# Fan_Power_Out.net
KiCad netlist of a schematic drawn in Altium Designer
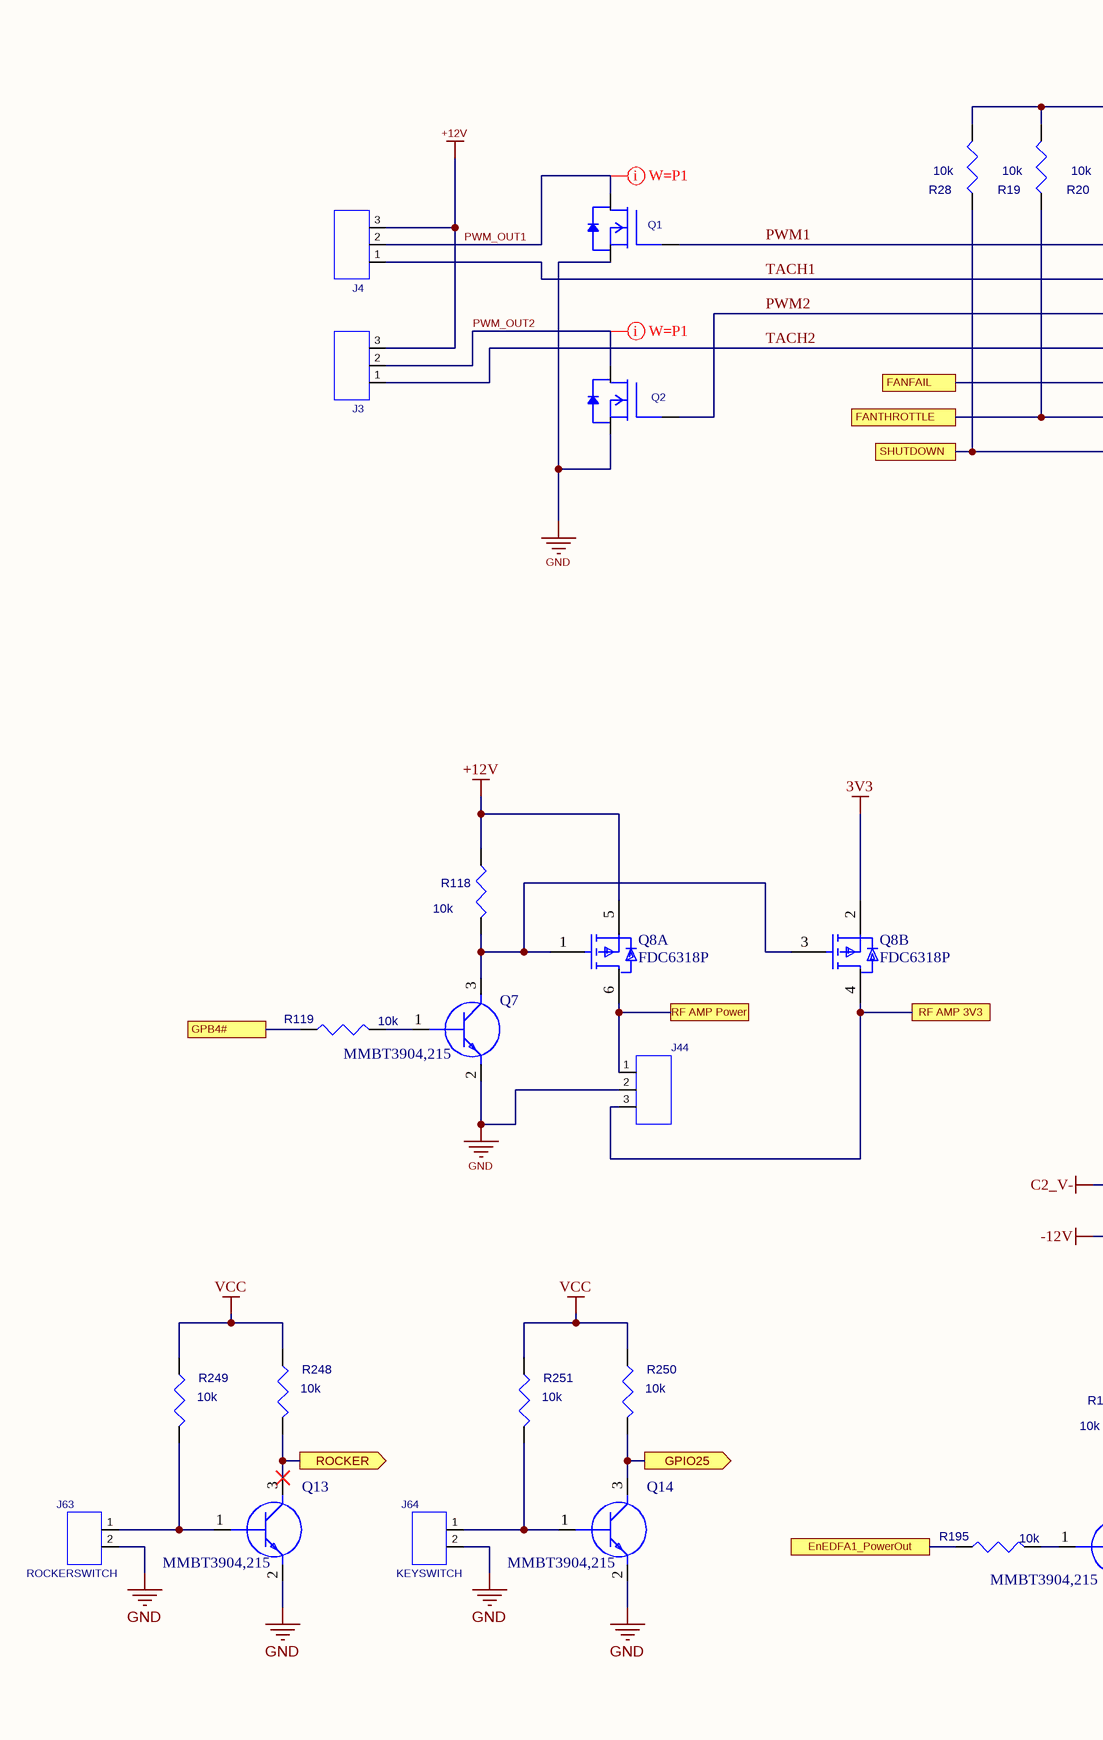
[diagram p0: Fan & Power Out.SchDoc, left]
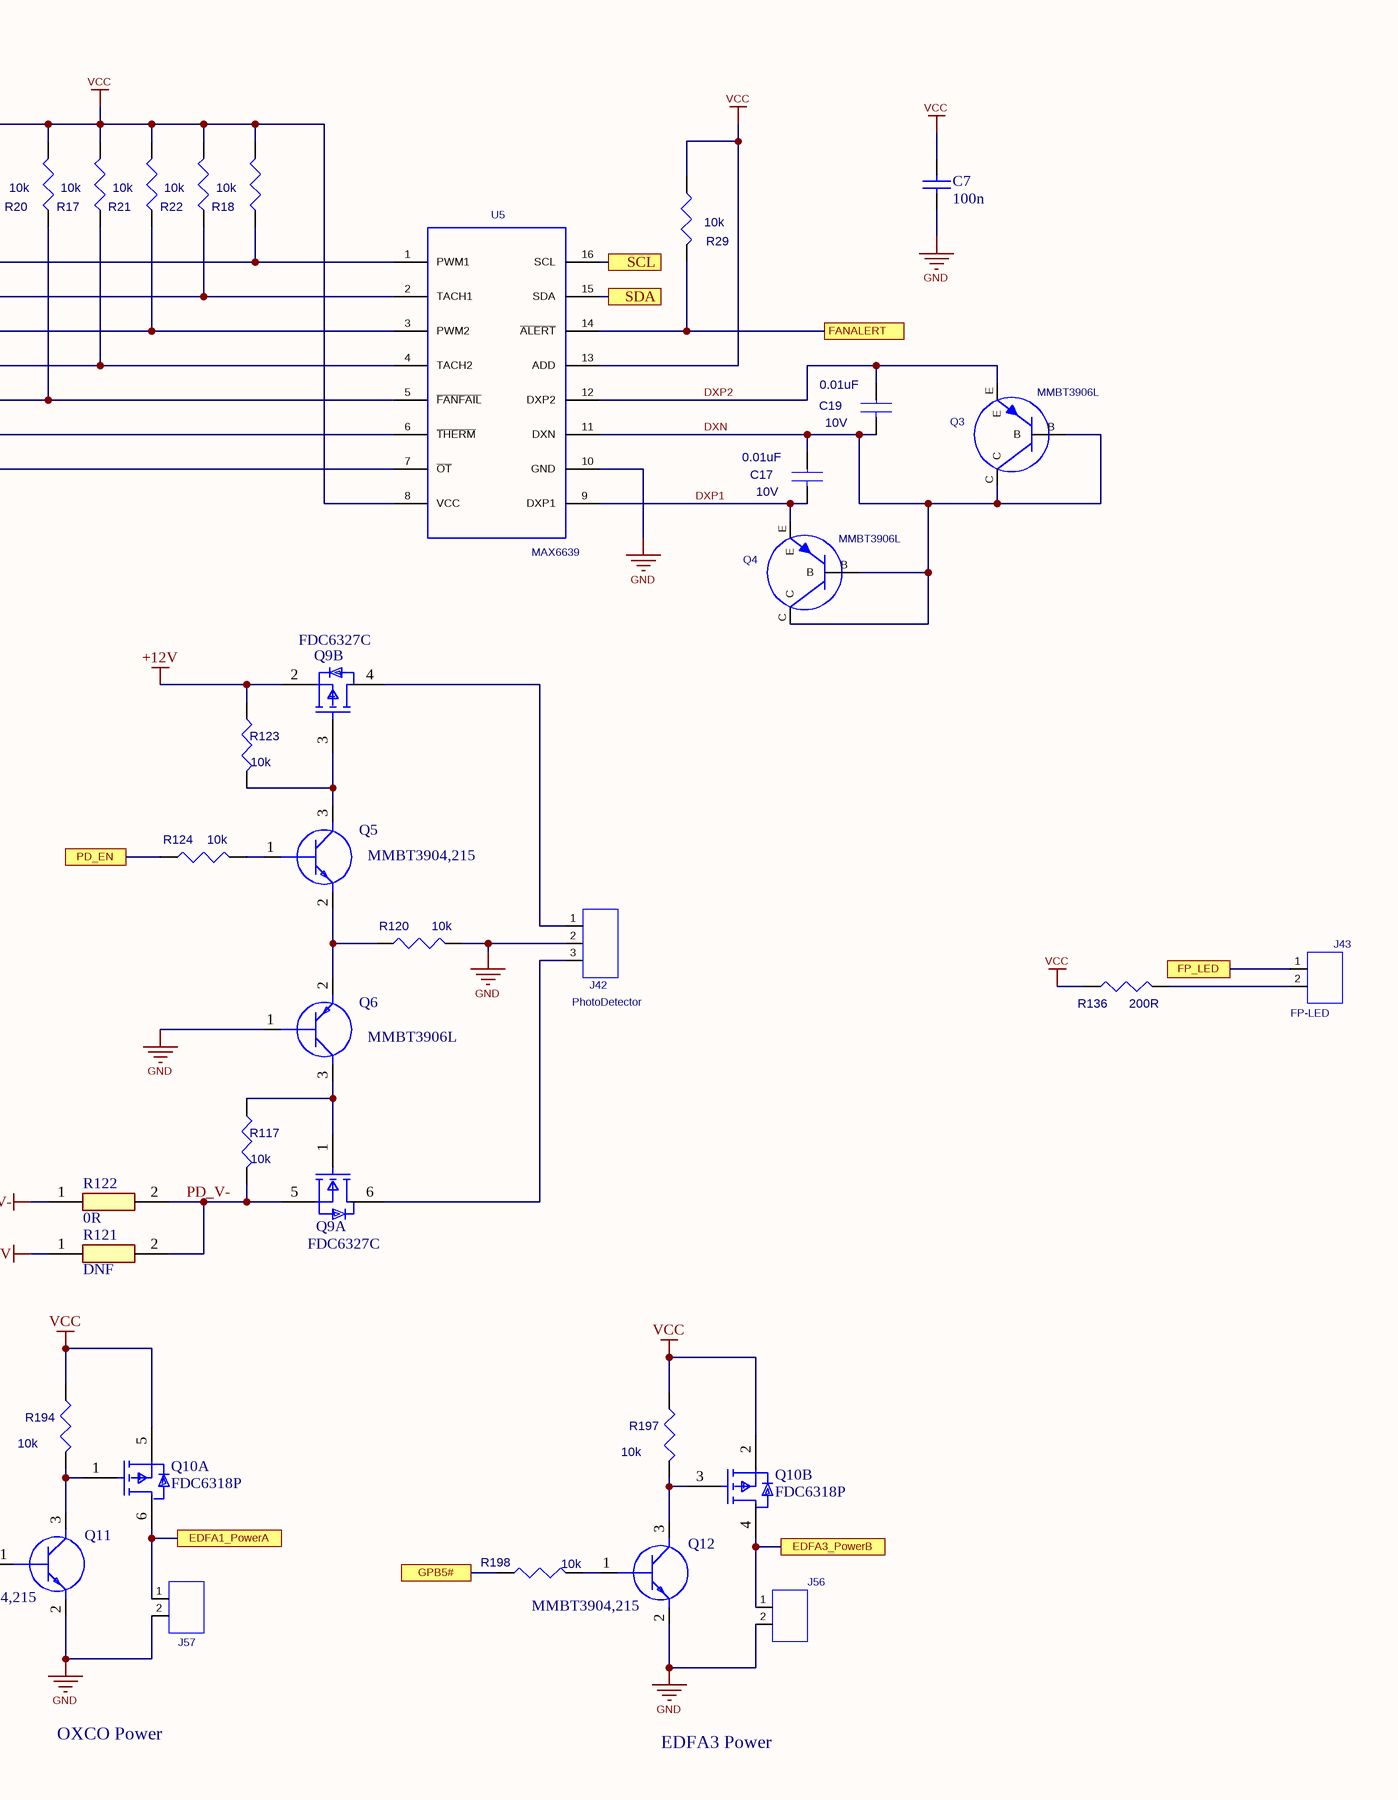
[diagram p1: Fan & Power Out.SchDoc, right]

(export (version "E")
  (design (tool "Eeschema 10.0.6"))
  (components
    (comp (ref "C7")
      (value "100n")
      (footprint "CAPC1608X90X35LL15T15")
      (description "Chip Capacitor, 100 nF, +/- 10%, 50 V, -55 to 125 degC, 0603 (1608 Metric), RoHS, Tape and Reel")
      (fields (field (name "TOLERANCE") "10%") (field (name "MANUFACTURER") "KEMET"))
      (libsource (lib "xDAC_Carrier") (part "CMP-1035-02592-3"))
    )
    (comp (ref "C17")
      (value "0.01uF")
      (footprint "CC0603N")
      (description "CAP.,0.01uF,X5R,10V,10%,0603")
      (fields
        (field (name "TOLERANCE") "10%")
        (field (name "RATED_VOLTAGE") "10V")
        (field (name "MANUFACTURER") "AVX")
      )
      (libsource (lib "xDAC_Carrier") (part "CAP"))
    )
    (comp (ref "C19")
      (value "0.01uF")
      (footprint "CC0603N")
      (description "CAP.,0.01uF,X5R,10V,10%,0603")
      (fields
        (field (name "TOLERANCE") "10%")
        (field (name "RATED_VOLTAGE") "10V")
        (field (name "MANUFACTURER") "AVX")
      )
      (libsource (lib "xDAC_Carrier") (part "CAP"))
    )
    (comp (ref "J3")
      (value "CON03")
      (footprint "AE-6410-3W-VERTICAL")
      (description "3 pin Connector")
      (fields (field (name "MANUFACTURER") "Molex") (field (name "PART NO") "22-29-2031"))
      (libsource (lib "xDAC_Carrier") (part "CON03"))
    )
    (comp (ref "J4")
      (value "CON03")
      (footprint "AE-6410-3W-VERTICAL")
      (description "3 pin Connector")
      (fields (field (name "MANUFACTURER") "Molex") (field (name "PART NO") "22-29-2031"))
      (libsource (lib "xDAC_Carrier") (part "CON03"))
    )
    (comp (ref "J42")
      (value "PhotoDetector")
      (footprint "AE-6410-3W-VERTICAL")
      (description "3 pin Connector")
      (fields (field (name "MANUFACTURER") "Molex") (field (name "PART NO") "22-29-2031"))
      (libsource (lib "xDAC_Carrier") (part "CON03"))
    )
    (comp (ref "J43")
      (value "FP-LED")
      (footprint "AE-6410-2W-VERTICAL")
      (description "2 pin Connector, straight header, 2.54mm pitch")
      (fields (field (name "PART NO") "2211S-02G") (field (name "MANUFACTURER") "Multicomp"))
      (libsource (lib "*") (part "CON02"))
    )
    (comp (ref "J44")
      (value "CON03")
      (footprint "AE-6410-3W-VERTICAL")
      (description "3 pin Connector")
      (fields (field (name "MANUFACTURER") "Molex") (field (name "PART NO") "22-29-2031"))
      (libsource (lib "xDAC_Carrier") (part "CON03"))
    )
    (comp (ref "J56")
      (value "EDFA3 Power")
      (footprint "AE-6410-2W-VERTICAL")
      (description "2 pin Connector")
      (fields (field (name "MANUFACTURER") "Molex") (field (name "PART NO") "22-29-2021"))
      (libsource (lib "xDAC_Carrier") (part "CON02"))
    )
    (comp (ref "J57")
      (value "OXCO Power")
      (footprint "AE-6410-2W-VERTICAL")
      (description "2 pin Connector")
      (fields (field (name "MANUFACTURER") "Molex") (field (name "PART NO") "22-29-2021"))
      (libsource (lib "xDAC_Carrier") (part "CON02"))
    )
    (comp (ref "J63")
      (value "ROCKERSWITCH")
      (footprint "AE-6410-2W-VERTICAL")
      (description "2 pin Connector, straight header, 2.54mm pitch")
      (fields (field (name "PART NO") "2211S-02G") (field (name "MANUFACTURER") "Multicomp"))
      (libsource (lib "*") (part "CON02"))
    )
    (comp (ref "J64")
      (value "KEYSWITCH")
      (footprint "AE-6410-2W-VERTICAL")
      (description "2 pin Connector, straight header, 2.54mm pitch")
      (fields (field (name "PART NO") "2211S-02G") (field (name "MANUFACTURER") "Multicomp"))
      (libsource (lib "*") (part "CON02"))
    )
    (comp (ref "Q1")
      (value "DMG3418L-7")
      (footprint "SOT95P240X110-3N")
      (description "MOSFET N-CH 30V 4A SOT23")
      (fields (field (name "MANUFACTURER") "Diodes Inc"))
      (libsource (lib "xDAC_Carrier") (part "DMG3418L-7"))
    )
    (comp (ref "Q2")
      (value "DMG3418L-7")
      (footprint "SOT95P240X110-3N")
      (description "MOSFET N-CH 30V 4A SOT23")
      (fields (field (name "MANUFACTURER") "Diodes Inc"))
      (libsource (lib "xDAC_Carrier") (part "DMG3418L-7"))
    )
    (comp (ref "Q3")
      (value "MMBT3906L")
      (footprint "MMBT3906L")
      (description "GENERAL PURPOSE PNP SILICON TRANSISTOR")
      (fields (field (name "PART NUMBER") "MMBT3906LT1G") (field (name "MANUFACTURER") "On Semi"))
      (libsource (lib "xDAC_Carrier") (part "MMBT3906L"))
    )
    (comp (ref "Q4")
      (value "MMBT3906L")
      (footprint "MMBT3906L")
      (description "GENERAL PURPOSE PNP SILICON TRANSISTOR")
      (fields (field (name "PART NUMBER") "MMBT3906LT1G") (field (name "MANUFACTURER") "On Semi"))
      (libsource (lib "xDAC_Carrier") (part "MMBT3906L"))
    )
    (comp (ref "Q5")
      (value "MMBT3904,215")
      (footprint "MMBT3904215")
      (description "Transistor BJT NPN")
      (fields (field (name "MOUSER PART NUMBER") "771-MMBT3904T/R"))
      (libsource (lib "xDAC_Carrier") (part "MMBT3904,215"))
    )
    (comp (ref "Q6")
      (value "MMBT3906L")
      (footprint "SOT96P237X111-3N")
      (description "Transistor BJT PNP")
      (fields
        (field (name "MANUFACTURER_PART_NUMBER") "MMBT3906LT1H")
        (field (name "MOUSER PART NUMBER") "863-MMBT3906LT1H")
      )
      (libsource (lib "xDAC_Carrier") (part "MMBT3906LT1H"))
    )
    (comp (ref "Q7")
      (value "MMBT3904,215")
      (footprint "MMBT3904215")
      (description "Transistor BJT NPN")
      (fields (field (name "MOUSER PART NUMBER") "771-MMBT3904T/R"))
      (libsource (lib "xDAC_Carrier") (part "MMBT3904,215"))
    )
    (comp (ref "Q8")
      (value "FDC6318P")
      (footprint "ON_Semi_419BL_0")
      (libsource (lib "xDAC_Carrier") (part "FDC6318P"))
    )
    (comp (ref "Q9")
      (value "FDC6327C")
      (footprint "SOT95P275X110-6N")
      (description "Integrated Circuit")
      (fields (field (name "MOUSER PART NUMBER") "512-FDC6327C"))
      (libsource (lib "xDAC_Carrier") (part "FDC6327C"))
    )
    (comp (ref "Q10")
      (value "FDC6318P")
      (footprint "ON_Semi_419BL_0")
      (libsource (lib "xDAC_Carrier") (part "FDC6318P"))
    )
    (comp (ref "Q11")
      (value "MMBT3904,215")
      (footprint "MMBT3904215")
      (description "Transistor BJT NPN")
      (fields (field (name "MOUSER PART NUMBER") "771-MMBT3904T/R"))
      (libsource (lib "xDAC_Carrier") (part "MMBT3904,215"))
    )
    (comp (ref "Q12")
      (value "MMBT3904,215")
      (footprint "MMBT3904215")
      (description "Transistor BJT NPN")
      (fields (field (name "MOUSER PART NUMBER") "771-MMBT3904T/R"))
      (libsource (lib "xDAC_Carrier") (part "MMBT3904,215"))
    )
    (comp (ref "Q13")
      (value "MMBT3904,215")
      (footprint "MMBT3904215")
      (description "Transistor BJT NPN")
      (fields (field (name "MOUSER PART NUMBER") "771-MMBT3904T/R"))
      (libsource (lib "Lyra_MB_PCB") (part "MMBT3904,215"))
    )
    (comp (ref "Q14")
      (value "MMBT3904,215")
      (footprint "MMBT3904215")
      (description "Transistor BJT NPN")
      (fields (field (name "MOUSER PART NUMBER") "771-MMBT3904T/R"))
      (libsource (lib "Lyra_MB_PCB") (part "MMBT3904,215"))
    )
    (comp (ref "R17")
      (value "10k")
      (footprint "CR0603N")
      (description "RES.,10k OHMS,1%,1/10W,0603")
      (fields (field (name "MANUFACTURER") "PANASONIC") (field (name "TOLERANCE") "1%"))
      (libsource (lib "xDAC_Carrier") (part "RES"))
    )
    (comp (ref "R18")
      (value "10k")
      (footprint "CR0603N")
      (description "RES.,10k OHMS,1%,1/10W,0603")
      (fields (field (name "MANUFACTURER") "PANASONIC") (field (name "TOLERANCE") "1%"))
      (libsource (lib "xDAC_Carrier") (part "RES"))
    )
    (comp (ref "R19")
      (value "10k")
      (footprint "CR0603N")
      (description "RES.,10k OHMS,1%,1/10W,0603")
      (fields (field (name "MANUFACTURER") "PANASONIC") (field (name "TOLERANCE") "1%"))
      (libsource (lib "xDAC_Carrier") (part "RES"))
    )
    (comp (ref "R20")
      (value "10k")
      (footprint "CR0603N")
      (description "RES.,10k OHMS,1%,1/10W,0603")
      (fields (field (name "MANUFACTURER") "PANASONIC") (field (name "TOLERANCE") "1%"))
      (libsource (lib "xDAC_Carrier") (part "RES"))
    )
    (comp (ref "R21")
      (value "10k")
      (footprint "CR0603N")
      (description "RES.,10k OHMS,1%,1/10W,0603")
      (fields (field (name "MANUFACTURER") "PANASONIC") (field (name "TOLERANCE") "1%"))
      (libsource (lib "xDAC_Carrier") (part "RES"))
    )
    (comp (ref "R22")
      (value "10k")
      (footprint "CR0603N")
      (description "RES.,10k OHMS,1%,1/10W,0603")
      (fields (field (name "MANUFACTURER") "PANASONIC") (field (name "TOLERANCE") "1%"))
      (libsource (lib "xDAC_Carrier") (part "RES"))
    )
    (comp (ref "R28")
      (value "10k")
      (footprint "CR0603N")
      (description "RES.,10k OHMS,1%,1/10W,0603")
      (fields (field (name "MANUFACTURER") "PANASONIC") (field (name "TOLERANCE") "1%"))
      (libsource (lib "xDAC_Carrier") (part "RES"))
    )
    (comp (ref "R29")
      (value "10k")
      (footprint "CR0603N")
      (description "RES.,10k OHMS,1%,1/10W,0603")
      (fields (field (name "MANUFACTURER") "PANASONIC") (field (name "TOLERANCE") "1%"))
      (libsource (lib "xDAC_Carrier") (part "RES"))
    )
    (comp (ref "R117")
      (value "10k")
      (footprint "CR0603N")
      (description "RES.,10k OHMS,1%,1/10W,0603")
      (fields (field (name "MANUFACTURER") "PANASONIC") (field (name "TOLERANCE") "1%"))
      (libsource (lib "xDAC_Carrier") (part "RES"))
    )
    (comp (ref "R118")
      (value "10k")
      (footprint "CR0603N")
      (description "RES.,10k OHMS,1%,1/10W,0603")
      (fields (field (name "MANUFACTURER") "PANASONIC") (field (name "TOLERANCE") "1%"))
      (libsource (lib "xDAC_Carrier") (part "RES"))
    )
    (comp (ref "R119")
      (value "10k")
      (footprint "CR0603N")
      (description "RES.,10k OHMS,1%,1/10W,0603")
      (fields (field (name "MANUFACTURER") "PANASONIC") (field (name "TOLERANCE") "1%"))
      (libsource (lib "xDAC_Carrier") (part "RES"))
    )
    (comp (ref "R120")
      (value "10k")
      (footprint "CR0603N")
      (description "RES.,10k OHMS,1%,1/10W,0603")
      (fields (field (name "MANUFACTURER") "PANASONIC") (field (name "TOLERANCE") "1%"))
      (libsource (lib "xDAC_Carrier") (part "RES"))
    )
    (comp (ref "R121")
      (value "DNF")
      (footprint "RESC1608X55N")
      (description "Resistor")
      (fields
        (field (name "MANUFACTURER_PART_NUMBER") "RC0603FR-070RL")
        (field (name "MOUSER PART NUMBER") "603-RC0603FR-070RL")
      )
      (libsource (lib "Pilot") (part "RC0603FR-070RL"))
    )
    (comp (ref "R122")
      (value "0R")
      (footprint "RESC1608X55N")
      (description "Resistor")
      (fields
        (field (name "MANUFACTURER_PART_NUMBER") "RC0603FR-070RL")
        (field (name "MOUSER PART NUMBER") "603-RC0603FR-070RL")
      )
      (libsource (lib "Pilot") (part "RC0603FR-070RL"))
    )
    (comp (ref "R123")
      (value "10k")
      (footprint "CR0603N")
      (description "RES.,10k OHMS,1%,1/10W,0603")
      (fields (field (name "MANUFACTURER") "PANASONIC") (field (name "TOLERANCE") "1%"))
      (libsource (lib "xDAC_Carrier") (part "RES"))
    )
    (comp (ref "R124")
      (value "10k")
      (footprint "CR0603N")
      (description "RES.,10k OHMS,1%,1/10W,0603")
      (fields (field (name "MANUFACTURER") "PANASONIC") (field (name "TOLERANCE") "1%"))
      (libsource (lib "xDAC_Carrier") (part "RES"))
    )
    (comp (ref "R136")
      (value "200R")
      (footprint "CR0603N")
      (description "RES.,200 OHMS,1%,1/10W,0603")
      (fields (field (name "MANUFACTURER") "PANASONIC") (field (name "TOLERANCE") "1%"))
      (libsource (lib "xDAC_Carrier") (part "RES"))
    )
    (comp (ref "R194")
      (value "10k")
      (footprint "CR0603N")
      (description "RES.,10k OHMS,1%,1/10W,0603")
      (fields (field (name "MANUFACTURER") "PANASONIC") (field (name "TOLERANCE") "1%"))
      (libsource (lib "xDAC_Carrier") (part "RES"))
    )
    (comp (ref "R195")
      (value "10k")
      (footprint "CR0603N")
      (description "RES.,10k OHMS,1%,1/10W,0603")
      (fields (field (name "MANUFACTURER") "PANASONIC") (field (name "TOLERANCE") "1%"))
      (libsource (lib "xDAC_Carrier") (part "RES"))
    )
    (comp (ref "R197")
      (value "10k")
      (footprint "CR0603N")
      (description "RES.,10k OHMS,1%,1/10W,0603")
      (fields (field (name "MANUFACTURER") "PANASONIC") (field (name "TOLERANCE") "1%"))
      (libsource (lib "xDAC_Carrier") (part "RES"))
    )
    (comp (ref "R198")
      (value "10k")
      (footprint "CR0603N")
      (description "RES.,10k OHMS,1%,1/10W,0603")
      (fields (field (name "MANUFACTURER") "PANASONIC") (field (name "TOLERANCE") "1%"))
      (libsource (lib "xDAC_Carrier") (part "RES"))
    )
    (comp (ref "R248")
      (value "10k")
      (footprint "CR0603N")
      (description "RES.,10k OHMS,1%,1/10W,0603")
      (fields (field (name "MANUFACTURER") "PANASONIC") (field (name "TOLERANCE") "1%"))
      (libsource (lib "xDAC_Carrier") (part "RES"))
    )
    (comp (ref "R249")
      (value "10k")
      (footprint "CR0603N")
      (description "RES.,10k OHMS,1%,1/10W,0603")
      (fields (field (name "MANUFACTURER") "PANASONIC") (field (name "TOLERANCE") "1%"))
      (libsource (lib "xDAC_Carrier") (part "RES"))
    )
    (comp (ref "R250")
      (value "10k")
      (footprint "CR0603N")
      (description "RES.,10k OHMS,1%,1/10W,0603")
      (fields (field (name "MANUFACTURER") "PANASONIC") (field (name "TOLERANCE") "1%"))
      (libsource (lib "xDAC_Carrier") (part "RES"))
    )
    (comp (ref "R251")
      (value "10k")
      (footprint "CR0603N")
      (description "RES.,10k OHMS,1%,1/10W,0603")
      (fields (field (name "MANUFACTURER") "PANASONIC") (field (name "TOLERANCE") "1%"))
      (libsource (lib "xDAC_Carrier") (part "RES"))
    )
    (comp (ref "U5")
      (value "MAX6639")
      (footprint "SOP63P602X173-16N")
      (fields (field (name "MANUFACTURER") "Maxim") (field (name "PART NO") "MAX6639FAEE+"))
      (libsource (lib "xDAC_Carrier") (part "MAX6639"))
    )
  )
  (nets
    (net (code "1") (name "+12V") (class "Default")
      (node (ref "J3") (pin "3") (pinfunction "3_3") (pintype "passive"))
      (node (ref "J4") (pin "3") (pinfunction "3_3") (pintype "passive"))
      (node (ref "Q8") (pin "5") (pinfunction "S1_5") (pintype "passive"))
      (node (ref "Q9") (pin "2") (pinfunction "S2_2") (pintype "passive"))
      (node (ref "R118") (pin "1") (pinfunction "1_1") (pintype "passive"))
      (node (ref "R123") (pin "1") (pinfunction "1_1") (pintype "passive"))
    )
    (net (code "2") (name "-12V") (class "Default")
      (node (ref "R121") (pin "1") (pinfunction "1_1") (pintype "passive"))
    )
    (net (code "3") (name "/DXN") (class "Default")
      (node (ref "C17") (pin "1") (pinfunction "1_1") (pintype "passive"))
      (node (ref "C19") (pin "2") (pinfunction "2_2") (pintype "passive"))
      (node (ref "Q3") (pin "B") (pinfunction "B_B") (pintype "passive"))
      (node (ref "Q3") (pin "C") (pinfunction "C_C") (pintype "passive"))
      (node (ref "Q4") (pin "B") (pinfunction "B_B") (pintype "passive"))
      (node (ref "Q4") (pin "C") (pinfunction "C_C") (pintype "passive"))
      (node (ref "U5") (pin "11") (pinfunction "DXN_11") (pintype "passive"))
    )
    (net (code "4") (name "/DXP1") (class "Default")
      (node (ref "C17") (pin "2") (pinfunction "2_2") (pintype "passive"))
      (node (ref "Q4") (pin "E") (pinfunction "E_E") (pintype "passive"))
      (node (ref "U5") (pin "9") (pinfunction "DXP1_9") (pintype "passive"))
    )
    (net (code "5") (name "/DXP2") (class "Default")
      (node (ref "C19") (pin "1") (pinfunction "1_1") (pintype "passive"))
      (node (ref "Q3") (pin "E") (pinfunction "E_E") (pintype "passive"))
      (node (ref "U5") (pin "12") (pinfunction "DXP2_12") (pintype "passive"))
    )
    (net (code "6") (name "/EDFA1_PowerA") (class "Default")
      (node (ref "J57") (pin "1") (pinfunction "1_1") (pintype "passive"))
      (node (ref "Q10") (pin "6") (pinfunction "D1_6") (pintype "passive"))
    )
    (net (code "7") (name "/EDFA3_PowerB") (class "Default")
      (node (ref "J56") (pin "1") (pinfunction "1_1") (pintype "passive"))
      (node (ref "Q10") (pin "4") (pinfunction "D2_4") (pintype "passive"))
    )
    (net (code "8") (name "/EnEDFA1_PowerOut") (class "Default")
      (node (ref "R195") (pin "1") (pinfunction "1_1") (pintype "passive"))
    )
    (net (code "9") (name "/FANALERT") (class "Default")
      (node (ref "R29") (pin "1") (pinfunction "1_1") (pintype "passive"))
      (node (ref "U5") (pin "14") (pinfunction "ALERT_14") (pintype "passive"))
    )
    (net (code "10") (name "/FANFAIL") (class "Default")
      (node (ref "R20") (pin "1") (pinfunction "1_1") (pintype "passive"))
      (node (ref "U5") (pin "5") (pinfunction "FANFAIL_5") (pintype "passive"))
    )
    (net (code "11") (name "/FANTHROTTLE") (class "Default")
      (node (ref "R19") (pin "1") (pinfunction "1_1") (pintype "passive"))
      (node (ref "U5") (pin "6") (pinfunction "THERM_6") (pintype "passive"))
    )
    (net (code "12") (name "/FP_LED") (class "Default")
      (node (ref "J43") (pin "1") (pinfunction "1_1") (pintype "passive"))
    )
    (net (code "13") (name "/GPB4#") (class "Default")
      (node (ref "R119") (pin "1") (pinfunction "1_1") (pintype "passive"))
    )
    (net (code "14") (name "/GPB5#") (class "Default")
      (node (ref "R198") (pin "1") (pinfunction "1_1") (pintype "passive"))
    )
    (net (code "15") (name "/GPIO25") (class "Default")
      (node (ref "Q14") (pin "3") (pinfunction "C_3") (pintype "passive"))
      (node (ref "R250") (pin "2") (pinfunction "2_2") (pintype "passive"))
    )
    (net (code "16") (name "/PD_EN") (class "Default")
      (node (ref "R124") (pin "1") (pinfunction "1_1") (pintype "passive"))
    )
    (net (code "17") (name "/PD_V-") (class "Default")
      (node (ref "Q9") (pin "5") (pinfunction "S2_5") (pintype "passive"))
      (node (ref "R117") (pin "2") (pinfunction "2_2") (pintype "passive"))
      (node (ref "R121") (pin "2") (pinfunction "2_2") (pintype "passive"))
      (node (ref "R122") (pin "2") (pinfunction "2_2") (pintype "passive"))
    )
    (net (code "18") (name "/PWM1") (class "Default")
      (node (ref "Q1") (pin "1") (pinfunction "1_1") (pintype "passive"))
      (node (ref "R18") (pin "1") (pinfunction "1_1") (pintype "passive"))
      (node (ref "U5") (pin "1") (pinfunction "PWM1_1") (pintype "passive"))
    )
    (net (code "19") (name "/PWM2") (class "Default")
      (node (ref "Q2") (pin "1") (pinfunction "1_1") (pintype "passive"))
      (node (ref "R21") (pin "1") (pinfunction "1_1") (pintype "passive"))
      (node (ref "U5") (pin "3") (pinfunction "PWM2_3") (pintype "passive"))
    )
    (net (code "20") (name "/PWM_OUT1") (class "Default")
      (node (ref "J4") (pin "2") (pinfunction "2_2") (pintype "passive"))
      (node (ref "Q1") (pin "3") (pinfunction "3_3") (pintype "passive"))
    )
    (net (code "21") (name "/PWM_OUT2") (class "Default")
      (node (ref "J3") (pin "2") (pinfunction "2_2") (pintype "passive"))
      (node (ref "Q2") (pin "3") (pinfunction "3_3") (pintype "passive"))
    )
    (net (code "22") (name "/RF AMP 3V3") (class "Default")
      (node (ref "J44") (pin "3") (pinfunction "3_3") (pintype "passive"))
      (node (ref "Q8") (pin "4") (pinfunction "D2_4") (pintype "passive"))
    )
    (net (code "23") (name "/RF AMP Power") (class "Default")
      (node (ref "J44") (pin "1") (pinfunction "1_1") (pintype "passive"))
      (node (ref "Q8") (pin "6") (pinfunction "D1_6") (pintype "passive"))
    )
    (net (code "24") (name "/ROCKER") (class "Default")
      (node (ref "Q13") (pin "3") (pinfunction "C_3") (pintype "passive"))
      (node (ref "R248") (pin "2") (pinfunction "2_2") (pintype "passive"))
    )
    (net (code "25") (name "/SCL") (class "Default")
      (node (ref "U5") (pin "16") (pinfunction "SCL_16") (pintype "passive"))
    )
    (net (code "26") (name "/SDA") (class "Default")
      (node (ref "U5") (pin "15") (pinfunction "SDA_15") (pintype "passive"))
    )
    (net (code "27") (name "/SHUTDOWN") (class "Default")
      (node (ref "R28") (pin "1") (pinfunction "1_1") (pintype "passive"))
      (node (ref "U5") (pin "7") (pinfunction "OT_7") (pintype "passive"))
    )
    (net (code "28") (name "/TACH1") (class "Default")
      (node (ref "J4") (pin "1") (pinfunction "1_1") (pintype "passive"))
      (node (ref "R22") (pin "1") (pinfunction "1_1") (pintype "passive"))
      (node (ref "U5") (pin "2") (pinfunction "TACH1_2") (pintype "passive"))
    )
    (net (code "29") (name "/TACH2") (class "Default")
      (node (ref "J3") (pin "1") (pinfunction "1_1") (pintype "passive"))
      (node (ref "R17") (pin "1") (pinfunction "1_1") (pintype "passive"))
      (node (ref "U5") (pin "4") (pinfunction "TACH2_4") (pintype "passive"))
    )
    (net (code "30") (name "3V3") (class "Default")
      (node (ref "Q8") (pin "2") (pinfunction "S2_2") (pintype "passive"))
    )
    (net (code "31") (name "C2_V-") (class "Default")
      (node (ref "R122") (pin "1") (pinfunction "1_1") (pintype "passive"))
    )
    (net (code "32") (name "GND") (class "Default")
      (node (ref "C7") (pin "2") (pinfunction "2_2") (pintype "passive"))
      (node (ref "J42") (pin "2") (pinfunction "2_2") (pintype "passive"))
      (node (ref "J44") (pin "2") (pinfunction "2_2") (pintype "passive"))
      (node (ref "J56") (pin "2") (pinfunction "2_2") (pintype "passive"))
      (node (ref "J57") (pin "2") (pinfunction "2_2") (pintype "passive"))
      (node (ref "J63") (pin "2") (pinfunction "2_2") (pintype "passive"))
      (node (ref "J64") (pin "2") (pinfunction "2_2") (pintype "passive"))
      (node (ref "Q1") (pin "2") (pinfunction "2_2") (pintype "passive"))
      (node (ref "Q11") (pin "2") (pinfunction "E_2") (pintype "passive"))
      (node (ref "Q12") (pin "2") (pinfunction "E_2") (pintype "passive"))
      (node (ref "Q13") (pin "2") (pinfunction "E_2") (pintype "passive"))
      (node (ref "Q14") (pin "2") (pinfunction "E_2") (pintype "passive"))
      (node (ref "Q2") (pin "2") (pinfunction "2_2") (pintype "passive"))
      (node (ref "Q6") (pin "1") (pinfunction "B_1") (pintype "passive"))
      (node (ref "Q7") (pin "2") (pinfunction "E_2") (pintype "passive"))
      (node (ref "R120") (pin "2") (pinfunction "2_2") (pintype "passive"))
      (node (ref "U5") (pin "10") (pinfunction "GND_10") (pintype "passive"))
    )
    (net (code "33") (name "Net-(J43-Pad2)") (class "Default")
      (node (ref "J43") (pin "2") (pinfunction "2_2") (pintype "passive"))
      (node (ref "R136") (pin "2") (pinfunction "2_2") (pintype "passive"))
    )
    (net (code "34") (name "Net-(Q5-B)") (class "Default")
      (node (ref "Q5") (pin "1") (pinfunction "B_1") (pintype "passive"))
      (node (ref "R124") (pin "2") (pinfunction "2_2") (pintype "passive"))
    )
    (net (code "35") (name "Net-(Q5-C)") (class "Default")
      (node (ref "Q5") (pin "3") (pinfunction "C_3") (pintype "passive"))
      (node (ref "Q9") (pin "3") (pinfunction "G2_3") (pintype "passive"))
      (node (ref "R123") (pin "2") (pinfunction "2_2") (pintype "passive"))
    )
    (net (code "36") (name "Net-(Q5-E)") (class "Default")
      (node (ref "Q5") (pin "2") (pinfunction "E_2") (pintype "passive"))
      (node (ref "Q6") (pin "2") (pinfunction "E_2") (pintype "passive"))
      (node (ref "R120") (pin "1") (pinfunction "1_1") (pintype "passive"))
    )
    (net (code "37") (name "Net-(Q6-C)") (class "Default")
      (node (ref "Q6") (pin "3") (pinfunction "C_3") (pintype "passive"))
      (node (ref "Q9") (pin "1") (pinfunction "G2_1") (pintype "passive"))
      (node (ref "R117") (pin "1") (pinfunction "1_1") (pintype "passive"))
    )
    (net (code "38") (name "Net-(Q7-B)") (class "Default")
      (node (ref "Q7") (pin "1") (pinfunction "B_1") (pintype "passive"))
      (node (ref "R119") (pin "2") (pinfunction "2_2") (pintype "passive"))
    )
    (net (code "39") (name "Net-(Q7-C)") (class "Default")
      (node (ref "Q7") (pin "3") (pinfunction "C_3") (pintype "passive"))
      (node (ref "Q8") (pin "1") (pinfunction "G1_1") (pintype "passive"))
      (node (ref "Q8") (pin "3") (pinfunction "G2_3") (pintype "passive"))
      (node (ref "R118") (pin "2") (pinfunction "2_2") (pintype "passive"))
    )
    (net (code "40") (name "Net-(Q9A-D2)") (class "Default")
      (node (ref "J42") (pin "3") (pinfunction "3_3") (pintype "passive"))
      (node (ref "Q9") (pin "6") (pinfunction "D2_6") (pintype "passive"))
    )
    (net (code "41") (name "Net-(Q9B-D2)") (class "Default")
      (node (ref "J42") (pin "1") (pinfunction "1_1") (pintype "passive"))
      (node (ref "Q9") (pin "4") (pinfunction "D2_4") (pintype "passive"))
    )
    (net (code "42") (name "Net-(Q10A-G1)") (class "Default")
      (node (ref "Q10") (pin "1") (pinfunction "G1_1") (pintype "passive"))
      (node (ref "Q11") (pin "3") (pinfunction "C_3") (pintype "passive"))
      (node (ref "R194") (pin "2") (pinfunction "2_2") (pintype "passive"))
    )
    (net (code "43") (name "Net-(Q10B-G2)") (class "Default")
      (node (ref "Q10") (pin "3") (pinfunction "G2_3") (pintype "passive"))
      (node (ref "Q12") (pin "3") (pinfunction "C_3") (pintype "passive"))
      (node (ref "R197") (pin "2") (pinfunction "2_2") (pintype "passive"))
    )
    (net (code "44") (name "Net-(Q11-B)") (class "Default")
      (node (ref "Q11") (pin "1") (pinfunction "B_1") (pintype "passive"))
      (node (ref "R195") (pin "2") (pinfunction "2_2") (pintype "passive"))
    )
    (net (code "45") (name "Net-(Q12-B)") (class "Default")
      (node (ref "Q12") (pin "1") (pinfunction "B_1") (pintype "passive"))
      (node (ref "R198") (pin "2") (pinfunction "2_2") (pintype "passive"))
    )
    (net (code "46") (name "Net-(Q13-B)") (class "Default")
      (node (ref "J63") (pin "1") (pinfunction "1_1") (pintype "passive"))
      (node (ref "Q13") (pin "1") (pinfunction "B_1") (pintype "passive"))
      (node (ref "R249") (pin "2") (pinfunction "2_2") (pintype "passive"))
    )
    (net (code "47") (name "Net-(Q14-B)") (class "Default")
      (node (ref "J64") (pin "1") (pinfunction "1_1") (pintype "passive"))
      (node (ref "Q14") (pin "1") (pinfunction "B_1") (pintype "passive"))
      (node (ref "R251") (pin "2") (pinfunction "2_2") (pintype "passive"))
    )
    (net (code "48") (name "VCC") (class "Default")
      (node (ref "C7") (pin "1") (pinfunction "1_1") (pintype "passive"))
      (node (ref "Q10") (pin "2") (pinfunction "S2_2") (pintype "passive"))
      (node (ref "Q10") (pin "5") (pinfunction "S1_5") (pintype "passive"))
      (node (ref "R136") (pin "1") (pinfunction "1_1") (pintype "passive"))
      (node (ref "R17") (pin "2") (pinfunction "2_2") (pintype "passive"))
      (node (ref "R18") (pin "2") (pinfunction "2_2") (pintype "passive"))
      (node (ref "R19") (pin "2") (pinfunction "2_2") (pintype "passive"))
      (node (ref "R194") (pin "1") (pinfunction "1_1") (pintype "passive"))
      (node (ref "R197") (pin "1") (pinfunction "1_1") (pintype "passive"))
      (node (ref "R20") (pin "2") (pinfunction "2_2") (pintype "passive"))
      (node (ref "R21") (pin "2") (pinfunction "2_2") (pintype "passive"))
      (node (ref "R22") (pin "2") (pinfunction "2_2") (pintype "passive"))
      (node (ref "R248") (pin "1") (pinfunction "1_1") (pintype "passive"))
      (node (ref "R249") (pin "1") (pinfunction "1_1") (pintype "passive"))
      (node (ref "R250") (pin "1") (pinfunction "1_1") (pintype "passive"))
      (node (ref "R251") (pin "1") (pinfunction "1_1") (pintype "passive"))
      (node (ref "R28") (pin "2") (pinfunction "2_2") (pintype "passive"))
      (node (ref "R29") (pin "2") (pinfunction "2_2") (pintype "passive"))
      (node (ref "U5") (pin "13") (pinfunction "ADD_13") (pintype "passive"))
      (node (ref "U5") (pin "8") (pinfunction "VCC_8") (pintype "passive"))
    )
  )
)
